# blink1micro-programming-jig2.net
KiCad netlist of a schematic drawn in EAGLE
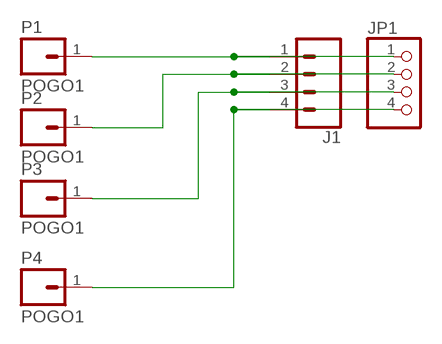
[diagram p0: schematic, sheet 1]

(export (version "E")
  (design (tool "Eeschema 10.0.6"))
  (components
    (comp (ref "J1")
      (value "CONN_04")
      (footprint "eagle-import:1X04")
      (libsource (lib "eagle-import") (part "CONN_04"))
    )
    (comp (ref "JP1")
      (value "PINHD-1X4/90")
      (footprint "eagle-import:1X04_90")
      (libsource (lib "eagle-import") (part "PINHD-1X4/90"))
    )
    (comp (ref "P1")
      (value "POGO1")
      (footprint "eagle-import:MILLMAX-0928-POGO-THRU")
      (libsource (lib "eagle-import") (part "POGO1"))
    )
    (comp (ref "P2")
      (value "POGO1")
      (footprint "eagle-import:MILLMAX-0928-POGO-THRU")
      (libsource (lib "eagle-import") (part "POGO1"))
    )
    (comp (ref "P3")
      (value "POGO1")
      (footprint "eagle-import:MILLMAX-0928-POGO-THRU")
      (libsource (lib "eagle-import") (part "POGO1"))
    )
    (comp (ref "P4")
      (value "POGO1")
      (footprint "eagle-import:MILLMAX-0928-POGO-THRU")
      (libsource (lib "eagle-import") (part "POGO1"))
    )
  )
  (nets
    (net (code "1") (name "Net-(J1-Pad1)") (class "Default")
      (node (ref "J1") (pin "1") (pinfunction "1_1") (pintype "passive"))
      (node (ref "JP1") (pin "1") (pinfunction "1_1") (pintype "passive"))
      (node (ref "P1") (pin "1") (pinfunction "1_1") (pintype "passive"))
    )
    (net (code "2") (name "Net-(J1-Pad2)") (class "Default")
      (node (ref "J1") (pin "2") (pinfunction "2_2") (pintype "passive"))
      (node (ref "JP1") (pin "2") (pinfunction "2_2") (pintype "passive"))
      (node (ref "P2") (pin "1") (pinfunction "1_1") (pintype "passive"))
    )
    (net (code "3") (name "Net-(J1-Pad3)") (class "Default")
      (node (ref "J1") (pin "3") (pinfunction "3_3") (pintype "passive"))
      (node (ref "JP1") (pin "3") (pinfunction "3_3") (pintype "passive"))
      (node (ref "P3") (pin "1") (pinfunction "1_1") (pintype "passive"))
    )
    (net (code "4") (name "Net-(J1-Pad4)") (class "Default")
      (node (ref "J1") (pin "4") (pinfunction "4_4") (pintype "passive"))
      (node (ref "JP1") (pin "4") (pinfunction "4_4") (pintype "passive"))
      (node (ref "P4") (pin "1") (pinfunction "1_1") (pintype "passive"))
    )
  )
)
